# Sheet1.net
KiCad netlist of a schematic drawn in Altium Designer
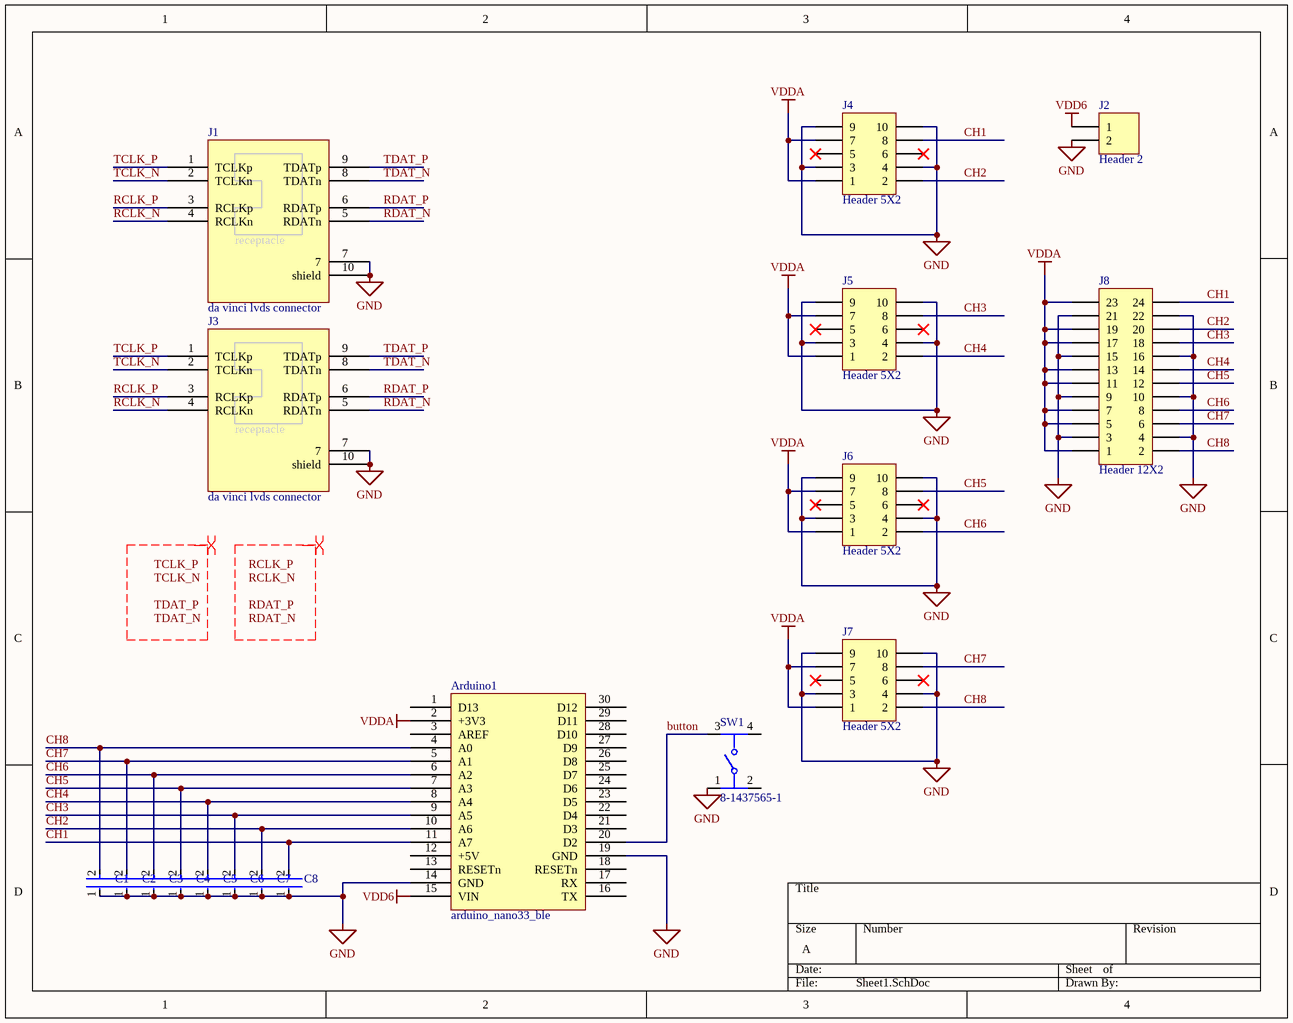
[diagram p0: Sheet1.SchDoc]

(export (version "E")
  (design (tool "Eeschema 10.0.6"))
  (components
    (comp (ref "Arduino1")
      (value "arduino_nano33_ble")
      (footprint "arduino_nano33_ble")
      (libsource (lib "Schlib1") (part "arduino_nano33_ble"))
    )
    (comp (ref "C1")
      (value "GRM155R71C104KA88D")
      (footprint "FP-GRM15-MFG")
      (description "CAP CER 0.1UF 16V X7R 0402")
      (fields
        (field (name "TOLERANCE") "10%")
        (field (name "OCTOPART") "https://octopart.com/grm155r71c104ka88d-murata-196880")
      )
      (libsource (lib "Altium Content Vault") (part "236180d848d6139a670b325ea6854c9"))
    )
    (comp (ref "C2")
      (value "GRM155R71C104KA88D")
      (footprint "FP-GRM15-MFG")
      (description "CAP CER 0.1UF 16V X7R 0402")
      (fields
        (field (name "TOLERANCE") "10%")
        (field (name "OCTOPART") "https://octopart.com/grm155r71c104ka88d-murata-196880")
      )
      (libsource (lib "Altium Content Vault") (part "236180d848d6139a670b325ea6854c9"))
    )
    (comp (ref "C3")
      (value "GRM155R71C104KA88D")
      (footprint "FP-GRM15-MFG")
      (description "CAP CER 0.1UF 16V X7R 0402")
      (fields
        (field (name "TOLERANCE") "10%")
        (field (name "OCTOPART") "https://octopart.com/grm155r71c104ka88d-murata-196880")
      )
      (libsource (lib "Altium Content Vault") (part "236180d848d6139a670b325ea6854c9"))
    )
    (comp (ref "C4")
      (value "GRM155R71C104KA88D")
      (footprint "FP-GRM15-MFG")
      (description "CAP CER 0.1UF 16V X7R 0402")
      (fields
        (field (name "TOLERANCE") "10%")
        (field (name "OCTOPART") "https://octopart.com/grm155r71c104ka88d-murata-196880")
      )
      (libsource (lib "Altium Content Vault") (part "236180d848d6139a670b325ea6854c9"))
    )
    (comp (ref "C5")
      (value "GRM155R71C104KA88D")
      (footprint "FP-GRM15-MFG")
      (description "CAP CER 0.1UF 16V X7R 0402")
      (fields
        (field (name "TOLERANCE") "10%")
        (field (name "OCTOPART") "https://octopart.com/grm155r71c104ka88d-murata-196880")
      )
      (libsource (lib "Altium Content Vault") (part "236180d848d6139a670b325ea6854c9"))
    )
    (comp (ref "C6")
      (value "GRM155R71C104KA88D")
      (footprint "FP-GRM15-MFG")
      (description "CAP CER 0.1UF 16V X7R 0402")
      (fields
        (field (name "TOLERANCE") "10%")
        (field (name "OCTOPART") "https://octopart.com/grm155r71c104ka88d-murata-196880")
      )
      (libsource (lib "Altium Content Vault") (part "236180d848d6139a670b325ea6854c9"))
    )
    (comp (ref "C7")
      (value "GRM155R71C104KA88D")
      (footprint "FP-GRM15-MFG")
      (description "CAP CER 0.1UF 16V X7R 0402")
      (fields
        (field (name "TOLERANCE") "10%")
        (field (name "OCTOPART") "https://octopart.com/grm155r71c104ka88d-murata-196880")
      )
      (libsource (lib "Altium Content Vault") (part "236180d848d6139a670b325ea6854c9"))
    )
    (comp (ref "C8")
      (value "GRM155R71C104KA88D")
      (footprint "FP-GRM15-MFG")
      (description "CAP CER 0.1UF 16V X7R 0402")
      (fields
        (field (name "TOLERANCE") "10%")
        (field (name "OCTOPART") "https://octopart.com/grm155r71c104ka88d-murata-196880")
      )
      (libsource (lib "Altium Content Vault") (part "236180d848d6139a670b325ea6854c9"))
    )
    (comp (ref "J1")
      (value "da vinci lvds connector")
      (footprint "1394b")
      (libsource (lib "Schlib1") (part "davinci_lvds"))
    )
    (comp (ref "J2")
      (value "Header 2")
      (footprint "jst_2mm")
      (description "Header, 2-Pin")
      (fields (field (name "PUBLISHER") "Altium Limited"))
      (libsource (lib "Miscellaneous Connectors") (part "Header 2"))
    )
    (comp (ref "J3")
      (value "da vinci lvds connector")
      (footprint "1394b")
      (libsource (lib "Schlib1") (part "davinci_lvds"))
    )
    (comp (ref "J4")
      (value "Header 5X2")
      (footprint "jst_pad10")
      (description "Header, 5-Pin, Dual row")
      (fields (field (name "PUBLISHER") "Altium Limited"))
      (libsource (lib "Miscellaneous Connectors") (part "Header 5X2"))
    )
    (comp (ref "J5")
      (value "Header 5X2")
      (footprint "jst_pad10")
      (description "Header, 5-Pin, Dual row")
      (fields (field (name "PUBLISHER") "Altium Limited"))
      (libsource (lib "Miscellaneous Connectors") (part "Header 5X2"))
    )
    (comp (ref "J6")
      (value "Header 5X2")
      (footprint "jst_pad10")
      (description "Header, 5-Pin, Dual row")
      (fields (field (name "PUBLISHER") "Altium Limited"))
      (libsource (lib "Miscellaneous Connectors") (part "Header 5X2"))
    )
    (comp (ref "J7")
      (value "Header 5X2")
      (footprint "jst_pad10")
      (description "Header, 5-Pin, Dual row")
      (fields (field (name "PUBLISHER") "Altium Limited"))
      (libsource (lib "Miscellaneous Connectors") (part "Header 5X2"))
    )
    (comp (ref "J8")
      (value "Header 12X2")
      (footprint "jst_pad24")
      (description "Header, 12-Pin, Dual row")
      (fields (field (name "PUBLISHER") "Altium Limited"))
      (libsource (lib "Miscellaneous Connectors") (part "Header 12X2"))
    )
    (comp (ref "SW1")
      (value "8-1437565-1")
      (footprint "FP-8-1437565-1-MFG")
      (description "SWITCH TACTILE SPST-NO 0.02A 15V")
      (libsource (lib "Altium Content Vault") (part "b8895f3f4cefb76e1819d2863dba89b"))
    )
  )
  (nets
    (net (code "1") (name "/CH1") (class "Default")
      (node (ref "Arduino1") (pin "11") (pinfunction "A7_11") (pintype "passive"))
      (node (ref "C8") (pin "2") (pinfunction "2_2") (pintype "passive"))
      (node (ref "J4") (pin "8") (pinfunction "8_8") (pintype "passive"))
      (node (ref "J8") (pin "24") (pinfunction "24_24") (pintype "passive"))
    )
    (net (code "2") (name "/CH2") (class "Default")
      (node (ref "Arduino1") (pin "10") (pinfunction "A6_10") (pintype "passive"))
      (node (ref "C7") (pin "2") (pinfunction "2_2") (pintype "passive"))
      (node (ref "J4") (pin "2") (pinfunction "2_2") (pintype "passive"))
      (node (ref "J8") (pin "20") (pinfunction "20_20") (pintype "passive"))
    )
    (net (code "3") (name "/CH3") (class "Default")
      (node (ref "Arduino1") (pin "9") (pinfunction "A5_9") (pintype "passive"))
      (node (ref "C6") (pin "2") (pinfunction "2_2") (pintype "passive"))
      (node (ref "J5") (pin "8") (pinfunction "8_8") (pintype "passive"))
      (node (ref "J8") (pin "18") (pinfunction "18_18") (pintype "passive"))
    )
    (net (code "4") (name "/CH4") (class "Default")
      (node (ref "Arduino1") (pin "8") (pinfunction "A4_8") (pintype "passive"))
      (node (ref "C5") (pin "2") (pinfunction "2_2") (pintype "passive"))
      (node (ref "J5") (pin "2") (pinfunction "2_2") (pintype "passive"))
      (node (ref "J8") (pin "14") (pinfunction "14_14") (pintype "passive"))
    )
    (net (code "5") (name "/CH5") (class "Default")
      (node (ref "Arduino1") (pin "7") (pinfunction "A3_7") (pintype "passive"))
      (node (ref "C4") (pin "2") (pinfunction "2_2") (pintype "passive"))
      (node (ref "J6") (pin "8") (pinfunction "8_8") (pintype "passive"))
      (node (ref "J8") (pin "12") (pinfunction "12_12") (pintype "passive"))
    )
    (net (code "6") (name "/CH6") (class "Default")
      (node (ref "Arduino1") (pin "6") (pinfunction "A2_6") (pintype "passive"))
      (node (ref "C3") (pin "2") (pinfunction "2_2") (pintype "passive"))
      (node (ref "J6") (pin "2") (pinfunction "2_2") (pintype "passive"))
      (node (ref "J8") (pin "8") (pinfunction "8_8") (pintype "passive"))
    )
    (net (code "7") (name "/CH7") (class "Default")
      (node (ref "Arduino1") (pin "5") (pinfunction "A1_5") (pintype "passive"))
      (node (ref "C2") (pin "2") (pinfunction "2_2") (pintype "passive"))
      (node (ref "J7") (pin "8") (pinfunction "8_8") (pintype "passive"))
      (node (ref "J8") (pin "6") (pinfunction "6_6") (pintype "passive"))
    )
    (net (code "8") (name "/CH8") (class "Default")
      (node (ref "Arduino1") (pin "4") (pinfunction "A0_4") (pintype "passive"))
      (node (ref "C1") (pin "2") (pinfunction "2_2") (pintype "passive"))
      (node (ref "J7") (pin "2") (pinfunction "2_2") (pintype "passive"))
      (node (ref "J8") (pin "2") (pinfunction "2_2") (pintype "passive"))
    )
    (net (code "9") (name "/RCLK_N") (class "Default")
      (node (ref "J1") (pin "4") (pinfunction "RCLKn_4") (pintype "passive"))
      (node (ref "J3") (pin "4") (pinfunction "RCLKn_4") (pintype "passive"))
    )
    (net (code "10") (name "/RCLK_P") (class "Default")
      (node (ref "J1") (pin "3") (pinfunction "RCLKp_3") (pintype "passive"))
      (node (ref "J3") (pin "3") (pinfunction "RCLKp_3") (pintype "passive"))
    )
    (net (code "11") (name "/RDAT_N") (class "Default")
      (node (ref "J1") (pin "5") (pinfunction "RDATn_5") (pintype "passive"))
      (node (ref "J3") (pin "5") (pinfunction "RDATn_5") (pintype "passive"))
    )
    (net (code "12") (name "/RDAT_P") (class "Default")
      (node (ref "J1") (pin "6") (pinfunction "RDATp_6") (pintype "passive"))
      (node (ref "J3") (pin "6") (pinfunction "RDATp_6") (pintype "passive"))
    )
    (net (code "13") (name "/TCLK_N") (class "Default")
      (node (ref "J1") (pin "2") (pinfunction "TCLKn_2") (pintype "passive"))
      (node (ref "J3") (pin "2") (pinfunction "TCLKn_2") (pintype "passive"))
    )
    (net (code "14") (name "/TCLK_P") (class "Default")
      (node (ref "J1") (pin "1") (pinfunction "TCLKp_1") (pintype "passive"))
      (node (ref "J3") (pin "1") (pinfunction "TCLKp_1") (pintype "passive"))
    )
    (net (code "15") (name "/TDAT_N") (class "Default")
      (node (ref "J1") (pin "8") (pinfunction "TDATn_8") (pintype "passive"))
      (node (ref "J3") (pin "8") (pinfunction "TDATn_8") (pintype "passive"))
    )
    (net (code "16") (name "/TDAT_P") (class "Default")
      (node (ref "J1") (pin "9") (pinfunction "TDATp_9") (pintype "passive"))
      (node (ref "J3") (pin "9") (pinfunction "TDATp_9") (pintype "passive"))
    )
    (net (code "17") (name "/button") (class "Default")
      (node (ref "Arduino1") (pin "20") (pinfunction "D2_20") (pintype "passive"))
      (node (ref "SW1") (pin "3") (pinfunction "3_3") (pintype "passive"))
    )
    (net (code "18") (name "GND") (class "Default")
      (node (ref "Arduino1") (pin "14") (pinfunction "GND_14") (pintype "passive"))
      (node (ref "Arduino1") (pin "19") (pinfunction "GND_19") (pintype "passive"))
      (node (ref "C1") (pin "1") (pinfunction "1_1") (pintype "passive"))
      (node (ref "C2") (pin "1") (pinfunction "1_1") (pintype "passive"))
      (node (ref "C3") (pin "1") (pinfunction "1_1") (pintype "passive"))
      (node (ref "C4") (pin "1") (pinfunction "1_1") (pintype "passive"))
      (node (ref "C5") (pin "1") (pinfunction "1_1") (pintype "passive"))
      (node (ref "C6") (pin "1") (pinfunction "1_1") (pintype "passive"))
      (node (ref "C7") (pin "1") (pinfunction "1_1") (pintype "passive"))
      (node (ref "C8") (pin "1") (pinfunction "1_1") (pintype "passive"))
      (node (ref "J1") (pin "10") (pinfunction "shield_10") (pintype "passive"))
      (node (ref "J1") (pin "7") (pinfunction "7_7") (pintype "passive"))
      (node (ref "J2") (pin "2") (pinfunction "2_2") (pintype "passive"))
      (node (ref "J3") (pin "10") (pinfunction "shield_10") (pintype "passive"))
      (node (ref "J3") (pin "7") (pinfunction "7_7") (pintype "passive"))
      (node (ref "J4") (pin "10") (pinfunction "10_10") (pintype "passive"))
      (node (ref "J4") (pin "3") (pinfunction "3_3") (pintype "passive"))
      (node (ref "J4") (pin "4") (pinfunction "4_4") (pintype "passive"))
      (node (ref "J4") (pin "9") (pinfunction "9_9") (pintype "passive"))
      (node (ref "J5") (pin "10") (pinfunction "10_10") (pintype "passive"))
      (node (ref "J5") (pin "3") (pinfunction "3_3") (pintype "passive"))
      (node (ref "J5") (pin "4") (pinfunction "4_4") (pintype "passive"))
      (node (ref "J5") (pin "9") (pinfunction "9_9") (pintype "passive"))
      (node (ref "J6") (pin "10") (pinfunction "10_10") (pintype "passive"))
      (node (ref "J6") (pin "3") (pinfunction "3_3") (pintype "passive"))
      (node (ref "J6") (pin "4") (pinfunction "4_4") (pintype "passive"))
      (node (ref "J6") (pin "9") (pinfunction "9_9") (pintype "passive"))
      (node (ref "J7") (pin "10") (pinfunction "10_10") (pintype "passive"))
      (node (ref "J7") (pin "3") (pinfunction "3_3") (pintype "passive"))
      (node (ref "J7") (pin "4") (pinfunction "4_4") (pintype "passive"))
      (node (ref "J7") (pin "9") (pinfunction "9_9") (pintype "passive"))
      (node (ref "J8") (pin "10") (pinfunction "10_10") (pintype "passive"))
      (node (ref "J8") (pin "15") (pinfunction "15_15") (pintype "passive"))
      (node (ref "J8") (pin "16") (pinfunction "16_16") (pintype "passive"))
      (node (ref "J8") (pin "21") (pinfunction "21_21") (pintype "passive"))
      (node (ref "J8") (pin "22") (pinfunction "22_22") (pintype "passive"))
      (node (ref "J8") (pin "3") (pinfunction "3_3") (pintype "passive"))
      (node (ref "J8") (pin "4") (pinfunction "4_4") (pintype "passive"))
      (node (ref "J8") (pin "9") (pinfunction "9_9") (pintype "passive"))
      (node (ref "SW1") (pin "1") (pinfunction "1_1") (pintype "passive"))
    )
    (net (code "19") (name "VDD6") (class "Default")
      (node (ref "Arduino1") (pin "15") (pinfunction "VIN_15") (pintype "passive"))
      (node (ref "J2") (pin "1") (pinfunction "1_1") (pintype "passive"))
    )
    (net (code "20") (name "VDDA") (class "Default")
      (node (ref "Arduino1") (pin "2") (pinfunction "+3V3_2") (pintype "passive"))
      (node (ref "J4") (pin "1") (pinfunction "1_1") (pintype "passive"))
      (node (ref "J4") (pin "7") (pinfunction "7_7") (pintype "passive"))
      (node (ref "J5") (pin "1") (pinfunction "1_1") (pintype "passive"))
      (node (ref "J5") (pin "7") (pinfunction "7_7") (pintype "passive"))
      (node (ref "J6") (pin "1") (pinfunction "1_1") (pintype "passive"))
      (node (ref "J6") (pin "7") (pinfunction "7_7") (pintype "passive"))
      (node (ref "J7") (pin "1") (pinfunction "1_1") (pintype "passive"))
      (node (ref "J7") (pin "7") (pinfunction "7_7") (pintype "passive"))
      (node (ref "J8") (pin "1") (pinfunction "1_1") (pintype "passive"))
      (node (ref "J8") (pin "11") (pinfunction "11_11") (pintype "passive"))
      (node (ref "J8") (pin "13") (pinfunction "13_13") (pintype "passive"))
      (node (ref "J8") (pin "17") (pinfunction "17_17") (pintype "passive"))
      (node (ref "J8") (pin "19") (pinfunction "19_19") (pintype "passive"))
      (node (ref "J8") (pin "23") (pinfunction "23_23") (pintype "passive"))
      (node (ref "J8") (pin "5") (pinfunction "5_5") (pintype "passive"))
      (node (ref "J8") (pin "7") (pinfunction "7_7") (pintype "passive"))
    )
    (net (code "21") (name "unconnected-(Arduino1-+5V-Pad12)") (class "Default")
      (node (ref "Arduino1") (pin "12") (pinfunction "+5V_12") (pintype "passive"))
    )
    (net (code "22") (name "unconnected-(Arduino1-AREF-Pad3)") (class "Default")
      (node (ref "Arduino1") (pin "3") (pinfunction "AREF_3") (pintype "passive"))
    )
    (net (code "23") (name "unconnected-(Arduino1-D3-Pad21)") (class "Default")
      (node (ref "Arduino1") (pin "21") (pinfunction "D3_21") (pintype "passive"))
    )
    (net (code "24") (name "unconnected-(Arduino1-D4-Pad22)") (class "Default")
      (node (ref "Arduino1") (pin "22") (pinfunction "D4_22") (pintype "passive"))
    )
    (net (code "25") (name "unconnected-(Arduino1-D5-Pad23)") (class "Default")
      (node (ref "Arduino1") (pin "23") (pinfunction "D5_23") (pintype "passive"))
    )
    (net (code "26") (name "unconnected-(Arduino1-D6-Pad24)") (class "Default")
      (node (ref "Arduino1") (pin "24") (pinfunction "D6_24") (pintype "passive"))
    )
    (net (code "27") (name "unconnected-(Arduino1-D7-Pad25)") (class "Default")
      (node (ref "Arduino1") (pin "25") (pinfunction "D7_25") (pintype "passive"))
    )
    (net (code "28") (name "unconnected-(Arduino1-D8-Pad26)") (class "Default")
      (node (ref "Arduino1") (pin "26") (pinfunction "D8_26") (pintype "passive"))
    )
    (net (code "29") (name "unconnected-(Arduino1-D9-Pad27)") (class "Default")
      (node (ref "Arduino1") (pin "27") (pinfunction "D9_27") (pintype "passive"))
    )
    (net (code "30") (name "unconnected-(Arduino1-D10-Pad28)") (class "Default")
      (node (ref "Arduino1") (pin "28") (pinfunction "D10_28") (pintype "passive"))
    )
    (net (code "31") (name "unconnected-(Arduino1-D11-Pad29)") (class "Default")
      (node (ref "Arduino1") (pin "29") (pinfunction "D11_29") (pintype "passive"))
    )
    (net (code "32") (name "unconnected-(Arduino1-D12-Pad30)") (class "Default")
      (node (ref "Arduino1") (pin "30") (pinfunction "D12_30") (pintype "passive"))
    )
    (net (code "33") (name "unconnected-(Arduino1-D13-Pad1)") (class "Default")
      (node (ref "Arduino1") (pin "1") (pinfunction "D13_1") (pintype "passive"))
    )
    (net (code "34") (name "unconnected-(Arduino1-RESETn-Pad13)") (class "Default")
      (node (ref "Arduino1") (pin "13") (pinfunction "RESETn_13") (pintype "passive"))
    )
    (net (code "35") (name "unconnected-(Arduino1-RESETn-Pad18)") (class "Default")
      (node (ref "Arduino1") (pin "18") (pinfunction "RESETn_18") (pintype "passive"))
    )
    (net (code "36") (name "unconnected-(Arduino1-RX-Pad17)") (class "Default")
      (node (ref "Arduino1") (pin "17") (pinfunction "RX_17") (pintype "passive"))
    )
    (net (code "37") (name "unconnected-(Arduino1-TX-Pad16)") (class "Default")
      (node (ref "Arduino1") (pin "16") (pinfunction "TX_16") (pintype "passive"))
    )
    (net (code "38") (name "unconnected-(J4-Pad5)") (class "Default")
      (node (ref "J4") (pin "5") (pinfunction "5_5") (pintype "passive+no_connect"))
    )
    (net (code "39") (name "unconnected-(J4-Pad6)") (class "Default")
      (node (ref "J4") (pin "6") (pinfunction "6_6") (pintype "passive+no_connect"))
    )
    (net (code "40") (name "unconnected-(J5-Pad5)") (class "Default")
      (node (ref "J5") (pin "5") (pinfunction "5_5") (pintype "passive+no_connect"))
    )
    (net (code "41") (name "unconnected-(J5-Pad6)") (class "Default")
      (node (ref "J5") (pin "6") (pinfunction "6_6") (pintype "passive+no_connect"))
    )
    (net (code "42") (name "unconnected-(J6-Pad5)") (class "Default")
      (node (ref "J6") (pin "5") (pinfunction "5_5") (pintype "passive+no_connect"))
    )
    (net (code "43") (name "unconnected-(J6-Pad6)") (class "Default")
      (node (ref "J6") (pin "6") (pinfunction "6_6") (pintype "passive+no_connect"))
    )
    (net (code "44") (name "unconnected-(J7-Pad5)") (class "Default")
      (node (ref "J7") (pin "5") (pinfunction "5_5") (pintype "passive+no_connect"))
    )
    (net (code "45") (name "unconnected-(J7-Pad6)") (class "Default")
      (node (ref "J7") (pin "6") (pinfunction "6_6") (pintype "passive+no_connect"))
    )
    (net (code "46") (name "unconnected-(SW1-Pad2)") (class "Default")
      (node (ref "SW1") (pin "2") (pinfunction "2_2") (pintype "passive"))
    )
    (net (code "47") (name "unconnected-(SW1-Pad4)") (class "Default")
      (node (ref "SW1") (pin "4") (pinfunction "4_4") (pintype "passive"))
    )
  )
)
